# USB_module.net
KiCad netlist of a schematic drawn in EAGLE
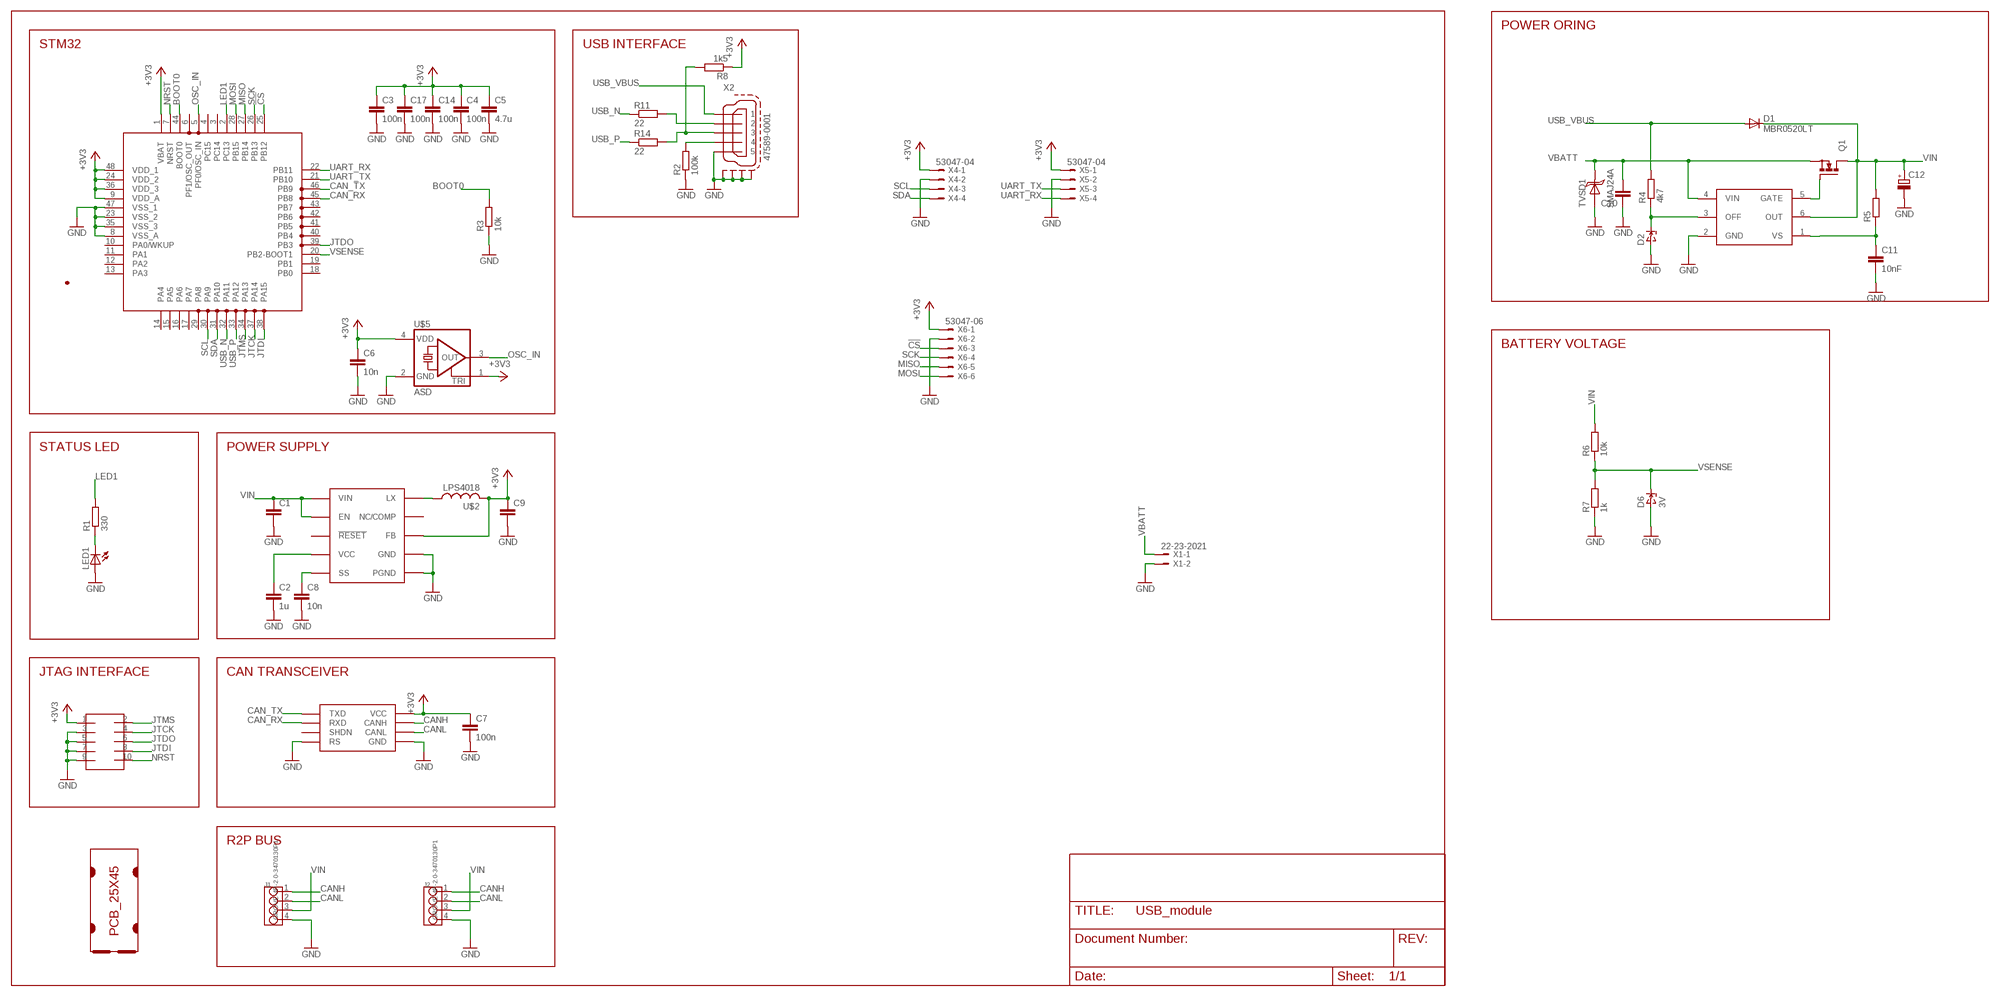
[diagram p0: schematic, sheet 1]

(export (version "E")
  (design (tool "Eeschema 10.0.6"))
  (components
    (comp (ref "C1")
      (value "C-EUC1206")
      (footprint "eagle-import:C1206")
      (libsource (lib "eagle-import") (part "C-EUC1206"))
    )
    (comp (ref "C2")
      (value "1u")
      (footprint "eagle-import:C0603")
      (libsource (lib "eagle-import") (part "C-EUC0603"))
    )
    (comp (ref "C3")
      (value "100n")
      (footprint "eagle-import:C0603")
      (libsource (lib "eagle-import") (part "C-EUC0603"))
    )
    (comp (ref "C4")
      (value "100n")
      (footprint "eagle-import:C0603")
      (libsource (lib "eagle-import") (part "C-EUC0603"))
    )
    (comp (ref "C5")
      (value "4.7u")
      (footprint "eagle-import:C0805")
      (libsource (lib "eagle-import") (part "C-EUC0805"))
    )
    (comp (ref "C6")
      (value "10n")
      (footprint "eagle-import:C0603")
      (libsource (lib "eagle-import") (part "C-EUC0603"))
    )
    (comp (ref "C7")
      (value "100n")
      (footprint "eagle-import:C0603")
      (libsource (lib "eagle-import") (part "C-EUC0603"))
    )
    (comp (ref "C8")
      (value "10n")
      (footprint "eagle-import:C0603")
      (libsource (lib "eagle-import") (part "C-EUC0603"))
    )
    (comp (ref "C9")
      (value "C-EUC0805")
      (footprint "eagle-import:C0805")
      (libsource (lib "eagle-import") (part "C-EUC0805"))
    )
    (comp (ref "C10")
      (value "C-EUC0805")
      (footprint "eagle-import:C0805")
      (libsource (lib "eagle-import") (part "C-EUC0805"))
    )
    (comp (ref "C11")
      (value "10nF")
      (footprint "eagle-import:C0603")
      (libsource (lib "eagle-import") (part "C-EUC0603"))
    )
    (comp (ref "C12")
      (value "CPOL-EUE3.5-8")
      (footprint "eagle-import:E3,5-8")
      (libsource (lib "eagle-import") (part "CPOL-EUE3.5-8"))
    )
    (comp (ref "C14")
      (value "100n")
      (footprint "eagle-import:C0603")
      (libsource (lib "eagle-import") (part "C-EUC0603"))
    )
    (comp (ref "C17")
      (value "100n")
      (footprint "eagle-import:C0603")
      (libsource (lib "eagle-import") (part "C-EUC0603"))
    )
    (comp (ref "D1")
      (value "MBR0520LT")
      (footprint "eagle-import:SOD123")
      (libsource (lib "eagle-import") (part "MBR0520LT"))
    )
    (comp (ref "D2")
      (value "ZENERSOD-323F")
      (footprint "eagle-import:SOD-323F")
      (libsource (lib "eagle-import") (part "ZENERSOD-323F"))
    )
    (comp (ref "D6")
      (value "3V")
      (footprint "eagle-import:SOD-323F")
      (libsource (lib "eagle-import") (part "ZENERSOD-323F"))
    )
    (comp (ref "J1")
      (value "GROVE-4P-2.0-3470130P1")
      (footprint "eagle-import:4P-2.0")
      (libsource (lib "eagle-import") (part "GROVE-4P-2.0-3470130P1"))
    )
    (comp (ref "J2")
      (value "GROVE-4P-2.0-3470130P1")
      (footprint "eagle-import:4P-2.0")
      (libsource (lib "eagle-import") (part "GROVE-4P-2.0-3470130P1"))
    )
    (comp (ref "LED1")
      (value "LEDCHIPLED_0805")
      (footprint "eagle-import:CHIPLED_0805")
      (libsource (lib "eagle-import") (part "LEDCHIPLED_0805"))
    )
    (comp (ref "Q1")
      (value "N-MOSFET-SO8S")
      (footprint "eagle-import:SO-08")
      (libsource (lib "eagle-import") (part "N-MOSFET-SO8S"))
    )
    (comp (ref "R1")
      (value "330")
      (footprint "eagle-import:R0603")
      (libsource (lib "eagle-import") (part "R-EU_R0603"))
    )
    (comp (ref "R2")
      (value "100k")
      (footprint "eagle-import:R0603")
      (libsource (lib "eagle-import") (part "R-EU_R0603"))
    )
    (comp (ref "R3")
      (value "10k")
      (footprint "eagle-import:R0603")
      (libsource (lib "eagle-import") (part "R-EU_R0603"))
    )
    (comp (ref "R4")
      (value "4k7")
      (footprint "eagle-import:R0603")
      (libsource (lib "eagle-import") (part "R-EU_R0603"))
    )
    (comp (ref "R5")
      (value "R-EU_R0603")
      (footprint "eagle-import:R0603")
      (libsource (lib "eagle-import") (part "R-EU_R0603"))
    )
    (comp (ref "R6")
      (value "10k")
      (footprint "eagle-import:R0603")
      (libsource (lib "eagle-import") (part "R-EU_R0603"))
    )
    (comp (ref "R7")
      (value "1k")
      (footprint "eagle-import:R0603")
      (libsource (lib "eagle-import") (part "R-EU_R0603"))
    )
    (comp (ref "R8")
      (value "1k5")
      (footprint "eagle-import:R0603")
      (libsource (lib "eagle-import") (part "R-EU_R0603"))
    )
    (comp (ref "R11")
      (value "22")
      (footprint "eagle-import:R0603")
      (libsource (lib "eagle-import") (part "R-EU_R0603"))
    )
    (comp (ref "R14")
      (value "22")
      (footprint "eagle-import:R0603")
      (libsource (lib "eagle-import") (part "R-EU_R0603"))
    )
    (comp (ref "SOT1")
      (value "MAX3051EKA")
      (footprint "eagle-import:SOT23-8L")
      (libsource (lib "eagle-import") (part "MAX3051EKA"))
    )
    (comp (ref "TVSD1")
      (value "SMAJ24A")
      (footprint "eagle-import:SMA")
      (libsource (lib "eagle-import") (part "TVSDSMA"))
    )
    (comp (ref "U$1")
      (value "PCB_25X45")
      (footprint "eagle-import:25X45")
      (libsource (lib "eagle-import") (part "PCB_25X45"))
    )
    (comp (ref "U$2")
      (value "LPS4018")
      (footprint "eagle-import:LPS4018")
      (libsource (lib "eagle-import") (part "LPS4018"))
    )
    (comp (ref "U$3")
      (value "MAX17501")
      (footprint "eagle-import:TDFN-10")
      (libsource (lib "eagle-import") (part "MAX17501"))
    )
    (comp (ref "U$4")
      (value "FTSH-105TH")
      (footprint "eagle-import:FTSH-105-TH")
      (libsource (lib "eagle-import") (part "FTSH-105TH"))
    )
    (comp (ref "U$5")
      (value "ASD")
      (footprint "eagle-import:2.5X2")
      (libsource (lib "eagle-import") (part "ASD"))
    )
    (comp (ref "U$6")
      (value "STM32F303C")
      (footprint "eagle-import:LQFP48")
      (libsource (lib "eagle-import") (part "STM32F303C"))
    )
    (comp (ref "U$7")
      (value "LM5050-1")
      (footprint "eagle-import:SOT23-6L")
      (libsource (lib "eagle-import") (part "LM5050-1"))
    )
    (comp (ref "X1")
      (value "22-23-2021")
      (footprint "eagle-import:22-23-2021")
      (fields (field (name "MF") "MOLEX"))
      (libsource (lib "eagle-import") (part "22-23-2021"))
    )
    (comp (ref "X2")
      (value "47589-0001")
      (footprint "eagle-import:47589-0001")
      (libsource (lib "eagle-import") (part "47589-0001"))
    )
    (comp (ref "X4")
      (value "53047-04")
      (footprint "eagle-import:53047-04")
      (fields (field (name "MF") "WALDOM/MOLEX") (field (name "MPN") "53047-0410"))
      (libsource (lib "eagle-import") (part "53?-04047"))
    )
    (comp (ref "X5")
      (value "53047-04")
      (footprint "eagle-import:53047-04")
      (fields (field (name "MF") "WALDOM/MOLEX") (field (name "MPN") "53047-0410"))
      (libsource (lib "eagle-import") (part "53?-04047"))
    )
    (comp (ref "X6")
      (value "53047-06")
      (footprint "eagle-import:53047-06")
      (fields (field (name "MPN") "53047-0610-C"))
      (libsource (lib "eagle-import") (part "53?-06047"))
    )
  )
  (nets
    (net (code "1") (name "+3V3") (class "Default")
      (node (ref "C14") (pin "1") (pinfunction "1_1") (pintype "passive"))
      (node (ref "C17") (pin "1") (pinfunction "1_1") (pintype "passive"))
      (node (ref "C3") (pin "1") (pinfunction "1_1") (pintype "passive"))
      (node (ref "C4") (pin "1") (pinfunction "1_1") (pintype "passive"))
      (node (ref "C5") (pin "1") (pinfunction "1_1") (pintype "passive"))
      (node (ref "C6") (pin "1") (pinfunction "1_1") (pintype "passive"))
      (node (ref "C7") (pin "1") (pinfunction "1_1") (pintype "passive"))
      (node (ref "C9") (pin "1") (pinfunction "1_1") (pintype "passive"))
      (node (ref "R8") (pin "1") (pinfunction "1_1") (pintype "passive"))
      (node (ref "SOT1") (pin "3") (pinfunction "VCC_3") (pintype "bidirectional"))
      (node (ref "U$2") (pin "P$2") (pinfunction "2_P$2") (pintype "passive"))
      (node (ref "U$3") (pin "P$5") (pinfunction "FB_P$5") (pintype "bidirectional"))
      (node (ref "U$4") (pin "1") (pinfunction "P$1_1") (pintype "bidirectional"))
      (node (ref "U$5") (pin "1") (pinfunction "TRI_1") (pintype "input"))
      (node (ref "U$5") (pin "4") (pinfunction "VDD_4") (pintype "power_in"))
      (node (ref "U$6") (pin "1") (pinfunction "VBAT_1") (pintype "bidirectional"))
      (node (ref "U$6") (pin "24") (pinfunction "VDD_2_24") (pintype "bidirectional"))
      (node (ref "U$6") (pin "36") (pinfunction "VDD_3_36") (pintype "bidirectional"))
      (node (ref "U$6") (pin "48") (pinfunction "VDD_1_48") (pintype "bidirectional"))
      (node (ref "U$6") (pin "9") (pinfunction "VDD_A_9") (pintype "bidirectional"))
      (node (ref "X4") (pin "1") (pinfunction "S_1") (pintype "passive"))
      (node (ref "X5") (pin "1") (pinfunction "S_1") (pintype "passive"))
      (node (ref "X6") (pin "1") (pinfunction "S_1") (pintype "passive"))
    )
    (net (code "2") (name "/BOOT0") (class "Default")
      (node (ref "R3") (pin "2") (pinfunction "2_2") (pintype "passive"))
      (node (ref "U$6") (pin "44") (pinfunction "BOOT0_44") (pintype "bidirectional"))
    )
    (net (code "3") (name "/CANH") (class "Default")
      (node (ref "J1") (pin "1") (pinfunction "1_1") (pintype "bidirectional"))
      (node (ref "J2") (pin "1") (pinfunction "1_1") (pintype "bidirectional"))
      (node (ref "SOT1") (pin "7") (pinfunction "CANH_7") (pintype "bidirectional"))
    )
    (net (code "4") (name "/CANL") (class "Default")
      (node (ref "J1") (pin "2") (pinfunction "2_2") (pintype "bidirectional"))
      (node (ref "J2") (pin "2") (pinfunction "2_2") (pintype "bidirectional"))
      (node (ref "SOT1") (pin "6") (pinfunction "CANL_6") (pintype "bidirectional"))
    )
    (net (code "5") (name "/CAN_RX") (class "Default")
      (node (ref "SOT1") (pin "4") (pinfunction "RXD_4") (pintype "bidirectional"))
      (node (ref "U$6") (pin "45") (pinfunction "PB8_45") (pintype "bidirectional"))
    )
    (net (code "6") (name "/CAN_TX") (class "Default")
      (node (ref "SOT1") (pin "1") (pinfunction "TXD_1") (pintype "bidirectional"))
      (node (ref "U$6") (pin "46") (pinfunction "PB9_46") (pintype "bidirectional"))
    )
    (net (code "7") (name "/JTCK") (class "Default")
      (node (ref "U$4") (pin "4") (pinfunction "P$4_4") (pintype "bidirectional"))
      (node (ref "U$6") (pin "37") (pinfunction "PA14_37") (pintype "bidirectional"))
    )
    (net (code "8") (name "/JTDI") (class "Default")
      (node (ref "U$4") (pin "8") (pinfunction "P$8_8") (pintype "bidirectional"))
      (node (ref "U$6") (pin "38") (pinfunction "PA15_38") (pintype "bidirectional"))
    )
    (net (code "9") (name "/JTDO") (class "Default")
      (node (ref "U$4") (pin "6") (pinfunction "P$6_6") (pintype "bidirectional"))
      (node (ref "U$6") (pin "39") (pinfunction "PB3_39") (pintype "bidirectional"))
    )
    (net (code "10") (name "/JTMS") (class "Default")
      (node (ref "U$4") (pin "2") (pinfunction "P$2_2") (pintype "bidirectional"))
      (node (ref "U$6") (pin "34") (pinfunction "PA13_34") (pintype "bidirectional"))
    )
    (net (code "11") (name "/LED1") (class "Default")
      (node (ref "R1") (pin "2") (pinfunction "2_2") (pintype "passive"))
      (node (ref "U$6") (pin "2") (pinfunction "PC13_2") (pintype "bidirectional"))
    )
    (net (code "12") (name "/MISO") (class "Default")
      (node (ref "U$6") (pin "27") (pinfunction "PB14_27") (pintype "bidirectional"))
      (node (ref "X6") (pin "5") (pinfunction "S_5") (pintype "passive"))
    )
    (net (code "13") (name "/MOSI") (class "Default")
      (node (ref "U$6") (pin "28") (pinfunction "PB15_28") (pintype "bidirectional"))
      (node (ref "X6") (pin "6") (pinfunction "S_6") (pintype "passive"))
    )
    (net (code "14") (name "/NRST") (class "Default")
      (node (ref "U$4") (pin "10") (pinfunction "P$10_10") (pintype "bidirectional"))
      (node (ref "U$6") (pin "7") (pinfunction "NRST_7") (pintype "bidirectional"))
    )
    (net (code "15") (name "/OSC_IN") (class "Default")
      (node (ref "U$5") (pin "3") (pinfunction "OUT_3") (pintype "output"))
      (node (ref "U$6") (pin "5") (pinfunction "PF0/OSC_IN_5") (pintype "bidirectional"))
    )
    (net (code "16") (name "/SCK") (class "Default")
      (node (ref "U$6") (pin "26") (pinfunction "PB13_26") (pintype "bidirectional"))
      (node (ref "X6") (pin "4") (pinfunction "S_4") (pintype "passive"))
    )
    (net (code "17") (name "/SCL") (class "Default")
      (node (ref "U$6") (pin "30") (pinfunction "PA9_30") (pintype "bidirectional"))
      (node (ref "X4") (pin "3") (pinfunction "S_3") (pintype "passive"))
    )
    (net (code "18") (name "/SDA") (class "Default")
      (node (ref "U$6") (pin "31") (pinfunction "PA10_31") (pintype "bidirectional"))
      (node (ref "X4") (pin "4") (pinfunction "S_4") (pintype "passive"))
    )
    (net (code "19") (name "/UART_RX") (class "Default")
      (node (ref "U$6") (pin "22") (pinfunction "PB11_22") (pintype "bidirectional"))
      (node (ref "X5") (pin "4") (pinfunction "S_4") (pintype "passive"))
    )
    (net (code "20") (name "/UART_TX") (class "Default")
      (node (ref "U$6") (pin "21") (pinfunction "PB10_21") (pintype "bidirectional"))
      (node (ref "X5") (pin "3") (pinfunction "S_3") (pintype "passive"))
    )
    (net (code "21") (name "/USB_N") (class "Default")
      (node (ref "R11") (pin "1") (pinfunction "1_1") (pintype "passive"))
      (node (ref "U$6") (pin "32") (pinfunction "PA11_32") (pintype "bidirectional"))
    )
    (net (code "22") (name "/USB_P") (class "Default")
      (node (ref "R14") (pin "1") (pinfunction "1_1") (pintype "passive"))
      (node (ref "U$6") (pin "33") (pinfunction "PA12_33") (pintype "bidirectional"))
    )
    (net (code "23") (name "/USB_VBUS") (class "Default")
      (node (ref "D1") (pin "A") (pinfunction "A_A") (pintype "passive"))
      (node (ref "R4") (pin "2") (pinfunction "2_2") (pintype "passive"))
      (node (ref "X2") (pin "1") (pinfunction "1_1") (pintype "passive"))
    )
    (net (code "24") (name "/VBATT") (class "Default")
      (node (ref "C10") (pin "2") (pinfunction "2_2") (pintype "passive"))
      (node (ref "Q1") (pin "1") (pinfunction "S_1") (pintype "passive"))
      (node (ref "Q1") (pin "2") (pinfunction "S_2") (pintype "passive"))
      (node (ref "Q1") (pin "3") (pinfunction "S_3") (pintype "passive"))
      (node (ref "TVSD1") (pin "C") (pinfunction "K_C") (pintype "bidirectional"))
      (node (ref "U$7") (pin "4") (pinfunction "VIN_4") (pintype "bidirectional"))
      (node (ref "X1") (pin "1") (pinfunction "S_1") (pintype "passive"))
    )
    (net (code "25") (name "/VIN") (class "Default")
      (node (ref "C1") (pin "1") (pinfunction "1_1") (pintype "passive"))
      (node (ref "C12") (pin "+") (pinfunction "+_+") (pintype "passive"))
      (node (ref "D1") (pin "C") (pinfunction "C_C") (pintype "passive"))
      (node (ref "J1") (pin "3") (pinfunction "3_3") (pintype "bidirectional"))
      (node (ref "J2") (pin "3") (pinfunction "3_3") (pintype "bidirectional"))
      (node (ref "Q1") (pin "5") (pinfunction "D_5") (pintype "passive"))
      (node (ref "Q1") (pin "6") (pinfunction "D_6") (pintype "passive"))
      (node (ref "Q1") (pin "7") (pinfunction "D_7") (pintype "passive"))
      (node (ref "Q1") (pin "8") (pinfunction "D_8") (pintype "passive"))
      (node (ref "R5") (pin "2") (pinfunction "2_2") (pintype "passive"))
      (node (ref "R6") (pin "2") (pinfunction "2_2") (pintype "passive"))
      (node (ref "U$3") (pin "P$2") (pinfunction "VIN_P$2") (pintype "bidirectional"))
      (node (ref "U$3") (pin "P$3") (pinfunction "EN_P$3") (pintype "bidirectional"))
      (node (ref "U$7") (pin "6") (pinfunction "OUT_6") (pintype "bidirectional"))
    )
    (net (code "26") (name "/VSENSE") (class "Default")
      (node (ref "D6") (pin "C") (pinfunction "C_C") (pintype "passive"))
      (node (ref "R6") (pin "1") (pinfunction "1_1") (pintype "passive"))
      (node (ref "R7") (pin "2") (pinfunction "2_2") (pintype "passive"))
      (node (ref "U$6") (pin "20") (pinfunction "PB2-BOOT1_20") (pintype "bidirectional"))
    )
    (net (code "27") (name "/~{CS}") (class "Default")
      (node (ref "U$6") (pin "25") (pinfunction "PB12_25") (pintype "bidirectional"))
      (node (ref "X6") (pin "3") (pinfunction "S_3") (pintype "passive"))
    )
    (net (code "28") (name "GND") (class "Default")
      (node (ref "C1") (pin "2") (pinfunction "2_2") (pintype "passive"))
      (node (ref "C10") (pin "1") (pinfunction "1_1") (pintype "passive"))
      (node (ref "C11") (pin "2") (pinfunction "2_2") (pintype "passive"))
      (node (ref "C12") (pin "-") (pinfunction "-_-") (pintype "passive"))
      (node (ref "C14") (pin "2") (pinfunction "2_2") (pintype "passive"))
      (node (ref "C17") (pin "2") (pinfunction "2_2") (pintype "passive"))
      (node (ref "C2") (pin "2") (pinfunction "2_2") (pintype "passive"))
      (node (ref "C3") (pin "2") (pinfunction "2_2") (pintype "passive"))
      (node (ref "C4") (pin "2") (pinfunction "2_2") (pintype "passive"))
      (node (ref "C5") (pin "2") (pinfunction "2_2") (pintype "passive"))
      (node (ref "C6") (pin "2") (pinfunction "2_2") (pintype "passive"))
      (node (ref "C7") (pin "2") (pinfunction "2_2") (pintype "passive"))
      (node (ref "C8") (pin "2") (pinfunction "2_2") (pintype "passive"))
      (node (ref "C9") (pin "2") (pinfunction "2_2") (pintype "passive"))
      (node (ref "D2") (pin "A") (pinfunction "A_A") (pintype "passive"))
      (node (ref "D6") (pin "A") (pinfunction "A_A") (pintype "passive"))
      (node (ref "J1") (pin "4") (pinfunction "4_4") (pintype "bidirectional"))
      (node (ref "J2") (pin "4") (pinfunction "4_4") (pintype "bidirectional"))
      (node (ref "LED1") (pin "A") (pinfunction "A_A") (pintype "passive"))
      (node (ref "R2") (pin "1") (pinfunction "1_1") (pintype "passive"))
      (node (ref "R3") (pin "1") (pinfunction "1_1") (pintype "passive"))
      (node (ref "R7") (pin "1") (pinfunction "1_1") (pintype "passive"))
      (node (ref "SOT1") (pin "2") (pinfunction "GND_2") (pintype "bidirectional"))
      (node (ref "SOT1") (pin "8") (pinfunction "RS_8") (pintype "bidirectional"))
      (node (ref "TVSD1") (pin "A") (pinfunction "A_A") (pintype "bidirectional"))
      (node (ref "U$3") (pin "P$1") (pinfunction "PGND_P$1") (pintype "bidirectional"))
      (node (ref "U$3") (pin "P$11") (pinfunction "PGND_P$11") (pintype "bidirectional"))
      (node (ref "U$3") (pin "P$9") (pinfunction "GND_P$9") (pintype "bidirectional"))
      (node (ref "U$4") (pin "3") (pinfunction "P$3_3") (pintype "bidirectional"))
      (node (ref "U$4") (pin "5") (pinfunction "P$5_5") (pintype "bidirectional"))
      (node (ref "U$4") (pin "7") (pinfunction "P$7_7") (pintype "bidirectional"))
      (node (ref "U$4") (pin "9") (pinfunction "P$9_9") (pintype "bidirectional"))
      (node (ref "U$5") (pin "2") (pinfunction "GND_2") (pintype "power_in"))
      (node (ref "U$6") (pin "23") (pinfunction "VSS_2_23") (pintype "bidirectional"))
      (node (ref "U$6") (pin "35") (pinfunction "VSS_3_35") (pintype "bidirectional"))
      (node (ref "U$6") (pin "47") (pinfunction "VSS_1_47") (pintype "bidirectional"))
      (node (ref "U$6") (pin "8") (pinfunction "VSS_A_8") (pintype "bidirectional"))
      (node (ref "U$7") (pin "2") (pinfunction "GND_2") (pintype "bidirectional"))
      (node (ref "X1") (pin "2") (pinfunction "S_2") (pintype "passive"))
      (node (ref "X2") (pin "5") (pinfunction "5_5") (pintype "passive"))
      (node (ref "X2") (pin "SHLD1") (pinfunction "SHLD1_SHLD1") (pintype "passive"))
      (node (ref "X2") (pin "SHLD2") (pinfunction "SHLD2_SHLD2") (pintype "passive"))
      (node (ref "X2") (pin "SHLD3") (pinfunction "SHLD3_SHLD3") (pintype "passive"))
      (node (ref "X2") (pin "SHLD4") (pinfunction "SHLD4_SHLD4") (pintype "passive"))
      (node (ref "X4") (pin "2") (pinfunction "S_2") (pintype "passive"))
      (node (ref "X5") (pin "2") (pinfunction "S_2") (pintype "passive"))
      (node (ref "X6") (pin "2") (pinfunction "S_2") (pintype "passive"))
    )
    (net (code "29") (name "Net-(LED1-PadC)") (class "Default")
      (node (ref "LED1") (pin "C") (pinfunction "C_C") (pintype "passive"))
      (node (ref "R1") (pin "1") (pinfunction "1_1") (pintype "passive"))
    )
    (net (code "30") (name "Net-(Q1-G)") (class "Default")
      (node (ref "Q1") (pin "4") (pinfunction "G_4") (pintype "passive"))
      (node (ref "U$7") (pin "5") (pinfunction "GATE_5") (pintype "bidirectional"))
    )
    (net (code "31") (name "Net-(R2-Pad2)") (class "Default")
      (node (ref "R2") (pin "2") (pinfunction "2_2") (pintype "passive"))
      (node (ref "X2") (pin "4") (pinfunction "4_4") (pintype "passive"))
    )
    (net (code "32") (name "Net-(R11-Pad2)") (class "Default")
      (node (ref "R11") (pin "2") (pinfunction "2_2") (pintype "passive"))
      (node (ref "X2") (pin "2") (pinfunction "2_2") (pintype "passive"))
    )
    (net (code "33") (name "Net-(R14-Pad2)") (class "Default")
      (node (ref "R14") (pin "2") (pinfunction "2_2") (pintype "passive"))
      (node (ref "R8") (pin "2") (pinfunction "2_2") (pintype "passive"))
      (node (ref "X2") (pin "3") (pinfunction "3_3") (pintype "passive"))
    )
    (net (code "34") (name "Net-(U$2-1)") (class "Default")
      (node (ref "U$2") (pin "P$1") (pinfunction "1_P$1") (pintype "passive"))
      (node (ref "U$3") (pin "P$10") (pinfunction "LX_P$10") (pintype "bidirectional"))
    )
    (net (code "35") (name "Net-(U$3-SS)") (class "Default")
      (node (ref "C8") (pin "1") (pinfunction "1_1") (pintype "passive"))
      (node (ref "U$3") (pin "P$6") (pinfunction "SS_P$6") (pintype "bidirectional"))
    )
    (net (code "36") (name "Net-(U$3-VCC)") (class "Default")
      (node (ref "C2") (pin "1") (pinfunction "1_1") (pintype "passive"))
      (node (ref "U$3") (pin "P$4") (pinfunction "VCC_P$4") (pintype "bidirectional"))
    )
    (net (code "37") (name "Net-(U$7-OFF)") (class "Default")
      (node (ref "D2") (pin "C") (pinfunction "C_C") (pintype "passive"))
      (node (ref "R4") (pin "1") (pinfunction "1_1") (pintype "passive"))
      (node (ref "U$7") (pin "3") (pinfunction "OFF_3") (pintype "bidirectional"))
    )
    (net (code "38") (name "Net-(U$7-VS)") (class "Default")
      (node (ref "C11") (pin "1") (pinfunction "1_1") (pintype "passive"))
      (node (ref "R5") (pin "1") (pinfunction "1_1") (pintype "passive"))
      (node (ref "U$7") (pin "1") (pinfunction "VS_1") (pintype "bidirectional"))
    )
    (net (code "39") (name "unconnected-(SOT1-SHDN-Pad5)") (class "Default")
      (node (ref "SOT1") (pin "5") (pinfunction "SHDN_5") (pintype "bidirectional"))
    )
    (net (code "40") (name "unconnected-(U$3-NC{slash}COMP-PadP$7)") (class "Default")
      (node (ref "U$3") (pin "P$7") (pinfunction "NC/COMP_P$7") (pintype "bidirectional"))
    )
    (net (code "41") (name "unconnected-(U$3-~{RESET}-PadP$8)") (class "Default")
      (node (ref "U$3") (pin "P$8") (pinfunction "~{RESET}_P$8") (pintype "bidirectional"))
    )
    (net (code "42") (name "unconnected-(U$6-PA0{slash}WKUP-Pad10)") (class "Default")
      (node (ref "U$6") (pin "10") (pinfunction "PA0/WKUP_10") (pintype "bidirectional"))
    )
    (net (code "43") (name "unconnected-(U$6-PA1-Pad11)") (class "Default")
      (node (ref "U$6") (pin "11") (pinfunction "PA1_11") (pintype "bidirectional"))
    )
    (net (code "44") (name "unconnected-(U$6-PA2-Pad12)") (class "Default")
      (node (ref "U$6") (pin "12") (pinfunction "PA2_12") (pintype "bidirectional"))
    )
    (net (code "45") (name "unconnected-(U$6-PA3-Pad13)") (class "Default")
      (node (ref "U$6") (pin "13") (pinfunction "PA3_13") (pintype "bidirectional"))
    )
    (net (code "46") (name "unconnected-(U$6-PA4-Pad14)") (class "Default")
      (node (ref "U$6") (pin "14") (pinfunction "PA4_14") (pintype "bidirectional"))
    )
    (net (code "47") (name "unconnected-(U$6-PA5-Pad15)") (class "Default")
      (node (ref "U$6") (pin "15") (pinfunction "PA5_15") (pintype "bidirectional"))
    )
    (net (code "48") (name "unconnected-(U$6-PA6-Pad16)") (class "Default")
      (node (ref "U$6") (pin "16") (pinfunction "PA6_16") (pintype "bidirectional"))
    )
    (net (code "49") (name "unconnected-(U$6-PA7-Pad17)") (class "Default")
      (node (ref "U$6") (pin "17") (pinfunction "PA7_17") (pintype "bidirectional"))
    )
    (net (code "50") (name "unconnected-(U$6-PA8-Pad29)") (class "Default")
      (node (ref "U$6") (pin "29") (pinfunction "PA8_29") (pintype "bidirectional"))
    )
    (net (code "51") (name "unconnected-(U$6-PB0-Pad18)") (class "Default")
      (node (ref "U$6") (pin "18") (pinfunction "PB0_18") (pintype "bidirectional"))
    )
    (net (code "52") (name "unconnected-(U$6-PB1-Pad19)") (class "Default")
      (node (ref "U$6") (pin "19") (pinfunction "PB1_19") (pintype "bidirectional"))
    )
    (net (code "53") (name "unconnected-(U$6-PB4-Pad40)") (class "Default")
      (node (ref "U$6") (pin "40") (pinfunction "PB4_40") (pintype "bidirectional"))
    )
    (net (code "54") (name "unconnected-(U$6-PB5-Pad41)") (class "Default")
      (node (ref "U$6") (pin "41") (pinfunction "PB5_41") (pintype "bidirectional"))
    )
    (net (code "55") (name "unconnected-(U$6-PB6-Pad42)") (class "Default")
      (node (ref "U$6") (pin "42") (pinfunction "PB6_42") (pintype "bidirectional"))
    )
    (net (code "56") (name "unconnected-(U$6-PB7-Pad43)") (class "Default")
      (node (ref "U$6") (pin "43") (pinfunction "PB7_43") (pintype "bidirectional"))
    )
    (net (code "57") (name "unconnected-(U$6-PC14-Pad3)") (class "Default")
      (node (ref "U$6") (pin "3") (pinfunction "PC14_3") (pintype "bidirectional"))
    )
    (net (code "58") (name "unconnected-(U$6-PC15-Pad4)") (class "Default")
      (node (ref "U$6") (pin "4") (pinfunction "PC15_4") (pintype "bidirectional"))
    )
    (net (code "59") (name "unconnected-(U$6-PF1{slash}OSC_OUT-Pad6)") (class "Default")
      (node (ref "U$6") (pin "6") (pinfunction "PF1/OSC_OUT_6") (pintype "bidirectional"))
    )
  )
)
